# uSD_CARD.net
KiCad netlist of a schematic drawn in Altium Designer
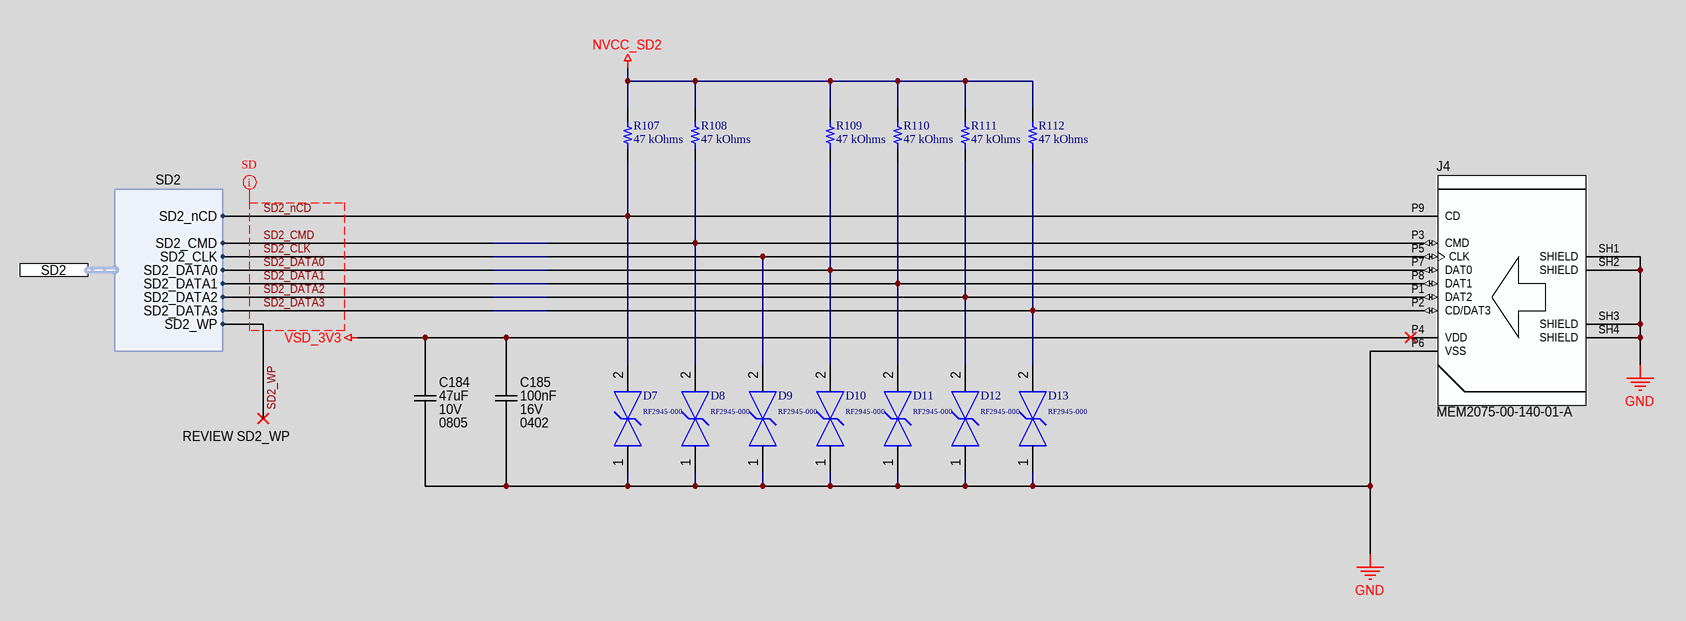
[diagram p0: uSD CARD.SchDoc]

(export (version "E")
  (design (tool "Eeschema 10.0.6"))
  (components
    (comp (ref "C184")
      (value "C2012X5R1A476M125AC")
      (footprint "CAP_0805_CAPC2012X12N")
      (description "Multilayer Ceramic Capacitor, 47 uF, 10 V, ± 20%, X5R, 0805 [2012 Metric]")
      (fields
        (field (name "MANUFACTURER") "TDK")
        (field (name "TOLERANCE") "20%")
        (field (name "VOLTAGE RATING (DC)") "10V")
        (field (name "CAPACITANCE") "47uF")
        (field (name "CASE CODE (IMPERIAL)") "0805")
      )
      (libsource (lib "Electronic Devices_LIB") (part "CAP_47UF_10V_X5R_0805"))
    )
    (comp (ref "C185")
      (value "CL05B104KO5NNNC")
      (footprint "CAP_0402_CAPC1005X05N")
      (description "Multilayer Ceramic Capacitor, 0.1 uF, 16 V, ± 10%, X7R, 0402 [1005 Metric]")
      (fields
        (field (name "MANUFACTURER") "Samsung")
        (field (name "TOLERANCE") "10%")
        (field (name "VOLTAGE RATING") "16V")
        (field (name "CAPACITANCE") "100nF")
        (field (name "CASE/PACKAGE") "0402")
      )
      (libsource (lib "Electronic Devices_LIB") (part "CAP_100NF_16V_X7R_0402"))
    )
    (comp (ref "D7")
      (value "RF2945-000")
      (footprint "FP-SESD0402-MFG")
      (description "TVS DIODE 7V 10V 0402")
      (fields
        (field (name "OCTOPART") "https://octopart.com/rf2945-000-littelfuse-56516902")
        (field (name "MANUFACTURER") "Littelfuse")
      )
      (libsource (lib "Altium Content Vault") (part "876f4347bf90aa6f500f43e3cd03972"))
    )
    (comp (ref "D8")
      (value "RF2945-000")
      (footprint "FP-SESD0402-MFG")
      (description "TVS DIODE 7V 10V 0402")
      (fields
        (field (name "OCTOPART") "https://octopart.com/rf2945-000-littelfuse-56516902")
        (field (name "MANUFACTURER") "Littelfuse")
      )
      (libsource (lib "Altium Content Vault") (part "876f4347bf90aa6f500f43e3cd03972"))
    )
    (comp (ref "D9")
      (value "RF2945-000")
      (footprint "FP-SESD0402-MFG")
      (description "TVS DIODE 7V 10V 0402")
      (fields
        (field (name "OCTOPART") "https://octopart.com/rf2945-000-littelfuse-56516902")
        (field (name "MANUFACTURER") "Littelfuse")
      )
      (libsource (lib "Altium Content Vault") (part "876f4347bf90aa6f500f43e3cd03972"))
    )
    (comp (ref "D10")
      (value "RF2945-000")
      (footprint "FP-SESD0402-MFG")
      (description "TVS DIODE 7V 10V 0402")
      (fields
        (field (name "OCTOPART") "https://octopart.com/rf2945-000-littelfuse-56516902")
        (field (name "MANUFACTURER") "Littelfuse")
      )
      (libsource (lib "Altium Content Vault") (part "876f4347bf90aa6f500f43e3cd03972"))
    )
    (comp (ref "D11")
      (value "RF2945-000")
      (footprint "FP-SESD0402-MFG")
      (description "TVS DIODE 7V 10V 0402")
      (fields
        (field (name "OCTOPART") "https://octopart.com/rf2945-000-littelfuse-56516902")
        (field (name "MANUFACTURER") "Littelfuse")
      )
      (libsource (lib "Altium Content Vault") (part "876f4347bf90aa6f500f43e3cd03972"))
    )
    (comp (ref "D12")
      (value "RF2945-000")
      (footprint "FP-SESD0402-MFG")
      (description "TVS DIODE 7V 10V 0402")
      (fields
        (field (name "OCTOPART") "https://octopart.com/rf2945-000-littelfuse-56516902")
        (field (name "MANUFACTURER") "Littelfuse")
      )
      (libsource (lib "Altium Content Vault") (part "876f4347bf90aa6f500f43e3cd03972"))
    )
    (comp (ref "D13")
      (value "RF2945-000")
      (footprint "FP-SESD0402-MFG")
      (description "TVS DIODE 7V 10V 0402")
      (fields
        (field (name "OCTOPART") "https://octopart.com/rf2945-000-littelfuse-56516902")
        (field (name "MANUFACTURER") "Littelfuse")
      )
      (libsource (lib "Altium Content Vault") (part "876f4347bf90aa6f500f43e3cd03972"))
    )
    (comp (ref "J4")
      (value "MEM2075-00-140-01-A")
      (footprint "CONN_MICROSD_GCT_MEM2075-00-140-01-A")
      (description "Memory Card Connectors Micro SD Push-Push, SMT, 1.40mm Profile, With Peg, Open Switch, T&R")
      (fields (field (name "MANUFACTURER") "Global Connector Technology"))
      (libsource (lib "Electronic Devices_LIB") (part "CONN_MICROSD_MEM2075-00-140-01-A"))
    )
    (comp (ref "R107")
      (value "47 kOhms")
      (footprint "RES 0402_1005")
      (description "RES 47K OHM 1% 1/16W 0402")
      (fields
        (field (name "PART NUMBER") "RMCF0402FT47K0")
        (field (name "MANUFACTURER") "Stackpole Electronics Inc")
      )
      (libsource (lib "Celestial Altium Library - altium_library") (part "Resistor"))
    )
    (comp (ref "R108")
      (value "47 kOhms")
      (footprint "RES 0402_1005")
      (description "RES 47K OHM 1% 1/16W 0402")
      (fields
        (field (name "PART NUMBER") "RMCF0402FT47K0")
        (field (name "MANUFACTURER") "Stackpole Electronics Inc")
      )
      (libsource (lib "Celestial Altium Library - altium_library") (part "Resistor"))
    )
    (comp (ref "R109")
      (value "47 kOhms")
      (footprint "RES 0402_1005")
      (description "RES 47K OHM 1% 1/16W 0402")
      (fields
        (field (name "PART NUMBER") "RMCF0402FT47K0")
        (field (name "MANUFACTURER") "Stackpole Electronics Inc")
      )
      (libsource (lib "Celestial Altium Library - altium_library") (part "Resistor"))
    )
    (comp (ref "R110")
      (value "47 kOhms")
      (footprint "RES 0402_1005")
      (description "RES 47K OHM 1% 1/16W 0402")
      (fields
        (field (name "PART NUMBER") "RMCF0402FT47K0")
        (field (name "MANUFACTURER") "Stackpole Electronics Inc")
      )
      (libsource (lib "Celestial Altium Library - altium_library") (part "Resistor"))
    )
    (comp (ref "R111")
      (value "47 kOhms")
      (footprint "RES 0402_1005")
      (description "RES 47K OHM 1% 1/16W 0402")
      (fields
        (field (name "PART NUMBER") "RMCF0402FT47K0")
        (field (name "MANUFACTURER") "Stackpole Electronics Inc")
      )
      (libsource (lib "Celestial Altium Library - altium_library") (part "Resistor"))
    )
    (comp (ref "R112")
      (value "47 kOhms")
      (footprint "RES 0402_1005")
      (description "RES 47K OHM 1% 1/16W 0402")
      (fields
        (field (name "PART NUMBER") "RMCF0402FT47K0")
        (field (name "MANUFACTURER") "Stackpole Electronics Inc")
      )
      (libsource (lib "Celestial Altium Library - altium_library") (part "Resistor"))
    )
  )
  (nets
    (net (code "2") (name "/SD2_CLK") (class "Default")
      (node (ref "D9") (pin "2") (pinfunction "2_2") (pintype "passive"))
      (node (ref "J4") (pin "P5") (pinfunction "CLK_P5") (pintype "bidirectional"))
    )
    (net (code "3") (name "/SD2_CMD") (class "Default")
      (node (ref "D8") (pin "2") (pinfunction "2_2") (pintype "passive"))
      (node (ref "J4") (pin "P3") (pinfunction "CMD_P3") (pintype "bidirectional"))
      (node (ref "R108") (pin "1") (pinfunction "1_1") (pintype "passive"))
    )
    (net (code "4") (name "/SD2_DATA0") (class "Default")
      (node (ref "D10") (pin "2") (pinfunction "2_2") (pintype "passive"))
      (node (ref "J4") (pin "P7") (pinfunction "DAT0_P7") (pintype "bidirectional"))
      (node (ref "R109") (pin "1") (pinfunction "1_1") (pintype "passive"))
    )
    (net (code "5") (name "/SD2_DATA1") (class "Default")
      (node (ref "D11") (pin "2") (pinfunction "2_2") (pintype "passive"))
      (node (ref "J4") (pin "P8") (pinfunction "DAT1_P8") (pintype "bidirectional"))
      (node (ref "R110") (pin "1") (pinfunction "1_1") (pintype "passive"))
    )
    (net (code "6") (name "/SD2_DATA2") (class "Default")
      (node (ref "D12") (pin "2") (pinfunction "2_2") (pintype "passive"))
      (node (ref "J4") (pin "P1") (pinfunction "DAT2_P1") (pintype "bidirectional"))
      (node (ref "R111") (pin "1") (pinfunction "1_1") (pintype "passive"))
    )
    (net (code "7") (name "/SD2_DATA3") (class "Default")
      (node (ref "D13") (pin "2") (pinfunction "2_2") (pintype "passive"))
      (node (ref "J4") (pin "P2") (pinfunction "CD/DAT3_P2") (pintype "bidirectional"))
      (node (ref "R112") (pin "1") (pinfunction "1_1") (pintype "passive"))
    )
    (net (code "9") (name "/SD2_nCD") (class "Default")
      (node (ref "D7") (pin "2") (pinfunction "2_2") (pintype "passive"))
      (node (ref "J4") (pin "P9") (pinfunction "CD_P9") (pintype "passive"))
      (node (ref "R107") (pin "1") (pinfunction "1_1") (pintype "passive"))
    )
    (net (code "11") (name "GND") (class "Default")
      (node (ref "C184") (pin "1") (pinfunction "1_1") (pintype "passive"))
      (node (ref "C185") (pin "1") (pinfunction "1_1") (pintype "passive"))
      (node (ref "D10") (pin "1") (pinfunction "1_1") (pintype "passive"))
      (node (ref "D11") (pin "1") (pinfunction "1_1") (pintype "passive"))
      (node (ref "D12") (pin "1") (pinfunction "1_1") (pintype "passive"))
      (node (ref "D13") (pin "1") (pinfunction "1_1") (pintype "passive"))
      (node (ref "D7") (pin "1") (pinfunction "1_1") (pintype "passive"))
      (node (ref "D8") (pin "1") (pinfunction "1_1") (pintype "passive"))
      (node (ref "D9") (pin "1") (pinfunction "1_1") (pintype "passive"))
      (node (ref "J4") (pin "P6") (pinfunction "VSS_P6") (pintype "power_in"))
      (node (ref "J4") (pin "SH1") (pinfunction "SHIELD_SH1") (pintype "power_in"))
      (node (ref "J4") (pin "SH2") (pinfunction "SHIELD_SH2") (pintype "power_in"))
      (node (ref "J4") (pin "SH3") (pinfunction "SHIELD_SH3") (pintype "power_in"))
      (node (ref "J4") (pin "SH4") (pinfunction "SHIELD_SH4") (pintype "power_in"))
    )
    (net (code "12") (name "NVCC_SD2") (class "Default")
      (node (ref "R107") (pin "2") (pinfunction "2_2") (pintype "passive"))
      (node (ref "R108") (pin "2") (pinfunction "2_2") (pintype "passive"))
      (node (ref "R109") (pin "2") (pinfunction "2_2") (pintype "passive"))
      (node (ref "R110") (pin "2") (pinfunction "2_2") (pintype "passive"))
      (node (ref "R111") (pin "2") (pinfunction "2_2") (pintype "passive"))
      (node (ref "R112") (pin "2") (pinfunction "2_2") (pintype "passive"))
    )
    (net (code "13") (name "VSD_3V3") (class "Default")
      (node (ref "C184") (pin "2") (pinfunction "2_2") (pintype "passive"))
      (node (ref "C185") (pin "2") (pinfunction "2_2") (pintype "passive"))
      (node (ref "J4") (pin "P4") (pinfunction "VDD_P4") (pintype "power_in"))
    )
  )
)
